# ESP.net
KiCad netlist of a schematic drawn in Altium Designer
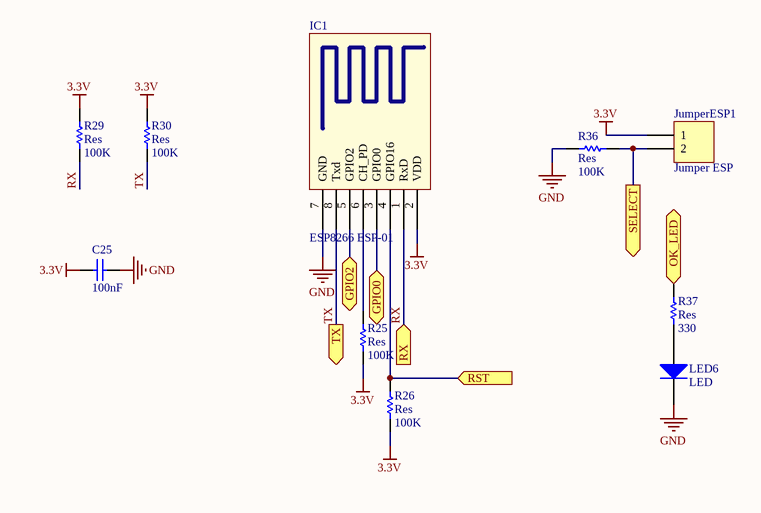
[diagram p0: ESP.SchDoc]

(export (version "E")
  (design (tool "Eeschema 10.0.6"))
  (components
    (comp (ref "C25")
      (value "100nF")
      (footprint "2012[0805]")
      (description "Capacitor")
      (fields (field (name "Comment") "Cap_UP") (field (name "PUBLISHER") "Altium Limited"))
      (libsource (lib "KN2CLib") (part "Cap_UP"))
    )
    (comp (ref "IC1")
      (value "ESP8266 ESP-01")
      (footprint "ESP8266 ESP-01")
      (libsource (lib "ESP8266") (part "ESP8266 ESP-01"))
    )
    (comp (ref "JumperESP1")
      (value "Jumper ESP")
      (footprint "HDR1X2")
      (description "Header, 2-Pin")
      (fields (field (name "PUBLISHER") "Altium Limited"))
      (libsource (lib "Miscellaneous Connectors") (part "Header 2"))
    )
    (comp (ref "LED6")
      (value "LED")
      (footprint "2012[0805]")
      (description "1 Amp General Purpose Rectifier")
      (fields (field (name "PUBLISHER") "Altium Limited"))
      (libsource (lib "KN2CLib") (part "Diode"))
    )
    (comp (ref "R25")
      (value "Res")
      (footprint "2012[0805]")
      (description "Semiconductor Resistor")
      (fields (field (name "ALTIUM_VALUE") "100K") (field (name "PUBLISHER") "Altium Limited"))
      (libsource (lib "KN2CLib") (part "Res"))
    )
    (comp (ref "R26")
      (value "Res")
      (footprint "2012[0805]")
      (description "Semiconductor Resistor")
      (fields (field (name "ALTIUM_VALUE") "100K") (field (name "PUBLISHER") "Altium Limited"))
      (libsource (lib "KN2CLib") (part "Res"))
    )
    (comp (ref "R29")
      (value "Res")
      (footprint "2012[0805]")
      (description "Semiconductor Resistor")
      (fields (field (name "ALTIUM_VALUE") "100K") (field (name "PUBLISHER") "Altium Limited"))
      (libsource (lib "KN2CLib") (part "Res"))
    )
    (comp (ref "R30")
      (value "Res")
      (footprint "2012[0805]")
      (description "Semiconductor Resistor")
      (fields (field (name "ALTIUM_VALUE") "100K") (field (name "PUBLISHER") "Altium Limited"))
      (libsource (lib "KN2CLib") (part "Res"))
    )
    (comp (ref "R36")
      (value "Res")
      (footprint "2012[0805]")
      (description "Semiconductor Resistor")
      (fields (field (name "ALTIUM_VALUE") "100K") (field (name "PUBLISHER") "Altium Limited"))
      (libsource (lib "KN2CLib") (part "Res"))
    )
    (comp (ref "R37")
      (value "Res")
      (footprint "2012[0805]")
      (description "Semiconductor Resistor")
      (fields (field (name "ALTIUM_VALUE") "330") (field (name "PUBLISHER") "Altium Limited"))
      (libsource (lib "KN2CLib") (part "Res"))
    )
  )
  (nets
    (net (code "1") (name "/GPIO0") (class "Default")
      (node (ref "IC1") (pin "3") (pinfunction "GPIO0_3") (pintype "passive"))
    )
    (net (code "2") (name "/GPIO2") (class "Default")
      (node (ref "IC1") (pin "5") (pinfunction "GPIO2_5") (pintype "passive"))
    )
    (net (code "3") (name "/OK_LED") (class "Default")
      (node (ref "R37") (pin "1") (pinfunction "1_1") (pintype "passive"))
    )
    (net (code "4") (name "/RST") (class "Default")
      (node (ref "IC1") (pin "4") (pinfunction "GPIO16_4") (pintype "passive"))
      (node (ref "R26") (pin "2") (pinfunction "2_2") (pintype "passive"))
    )
    (net (code "5") (name "/RX") (class "Default")
      (node (ref "IC1") (pin "1") (pinfunction "RxD_1") (pintype "passive"))
      (node (ref "R29") (pin "2") (pinfunction "2_2") (pintype "passive"))
    )
    (net (code "6") (name "/SELECT") (class "Default")
      (node (ref "JumperESP1") (pin "2") (pinfunction "2_2") (pintype "passive"))
      (node (ref "R36") (pin "2") (pinfunction "2_2") (pintype "passive"))
    )
    (net (code "7") (name "/TX") (class "Default")
      (node (ref "IC1") (pin "8") (pinfunction "Txd_8") (pintype "passive"))
      (node (ref "R30") (pin "2") (pinfunction "2_2") (pintype "passive"))
    )
    (net (code "8") (name "3.3V") (class "Default")
      (node (ref "C25") (pin "2") (pinfunction "2_2") (pintype "passive"))
      (node (ref "IC1") (pin "2") (pinfunction "VDD_2") (pintype "passive"))
      (node (ref "JumperESP1") (pin "1") (pinfunction "1_1") (pintype "passive"))
      (node (ref "R25") (pin "2") (pinfunction "2_2") (pintype "passive"))
      (node (ref "R26") (pin "1") (pinfunction "1_1") (pintype "passive"))
      (node (ref "R29") (pin "1") (pinfunction "1_1") (pintype "passive"))
      (node (ref "R30") (pin "1") (pinfunction "1_1") (pintype "passive"))
    )
    (net (code "9") (name "GND") (class "Default")
      (node (ref "C25") (pin "1") (pinfunction "1_1") (pintype "passive"))
      (node (ref "IC1") (pin "7") (pinfunction "GND_7") (pintype "passive"))
      (node (ref "LED6") (pin "2") (pinfunction "K_2") (pintype "passive"))
      (node (ref "R36") (pin "1") (pinfunction "1_1") (pintype "passive"))
    )
    (net (code "10") (name "Net-(IC1-CH_PD)") (class "Default")
      (node (ref "IC1") (pin "6") (pinfunction "CH_PD_6") (pintype "passive"))
      (node (ref "R25") (pin "1") (pinfunction "1_1") (pintype "passive"))
    )
    (net (code "11") (name "Net-(LED6-A)") (class "Default")
      (node (ref "LED6") (pin "1") (pinfunction "A_1") (pintype "passive"))
      (node (ref "R37") (pin "2") (pinfunction "2_2") (pintype "passive"))
    )
  )
)
